# Senior_Design_2.net
KiCad netlist of a schematic drawn in EAGLE
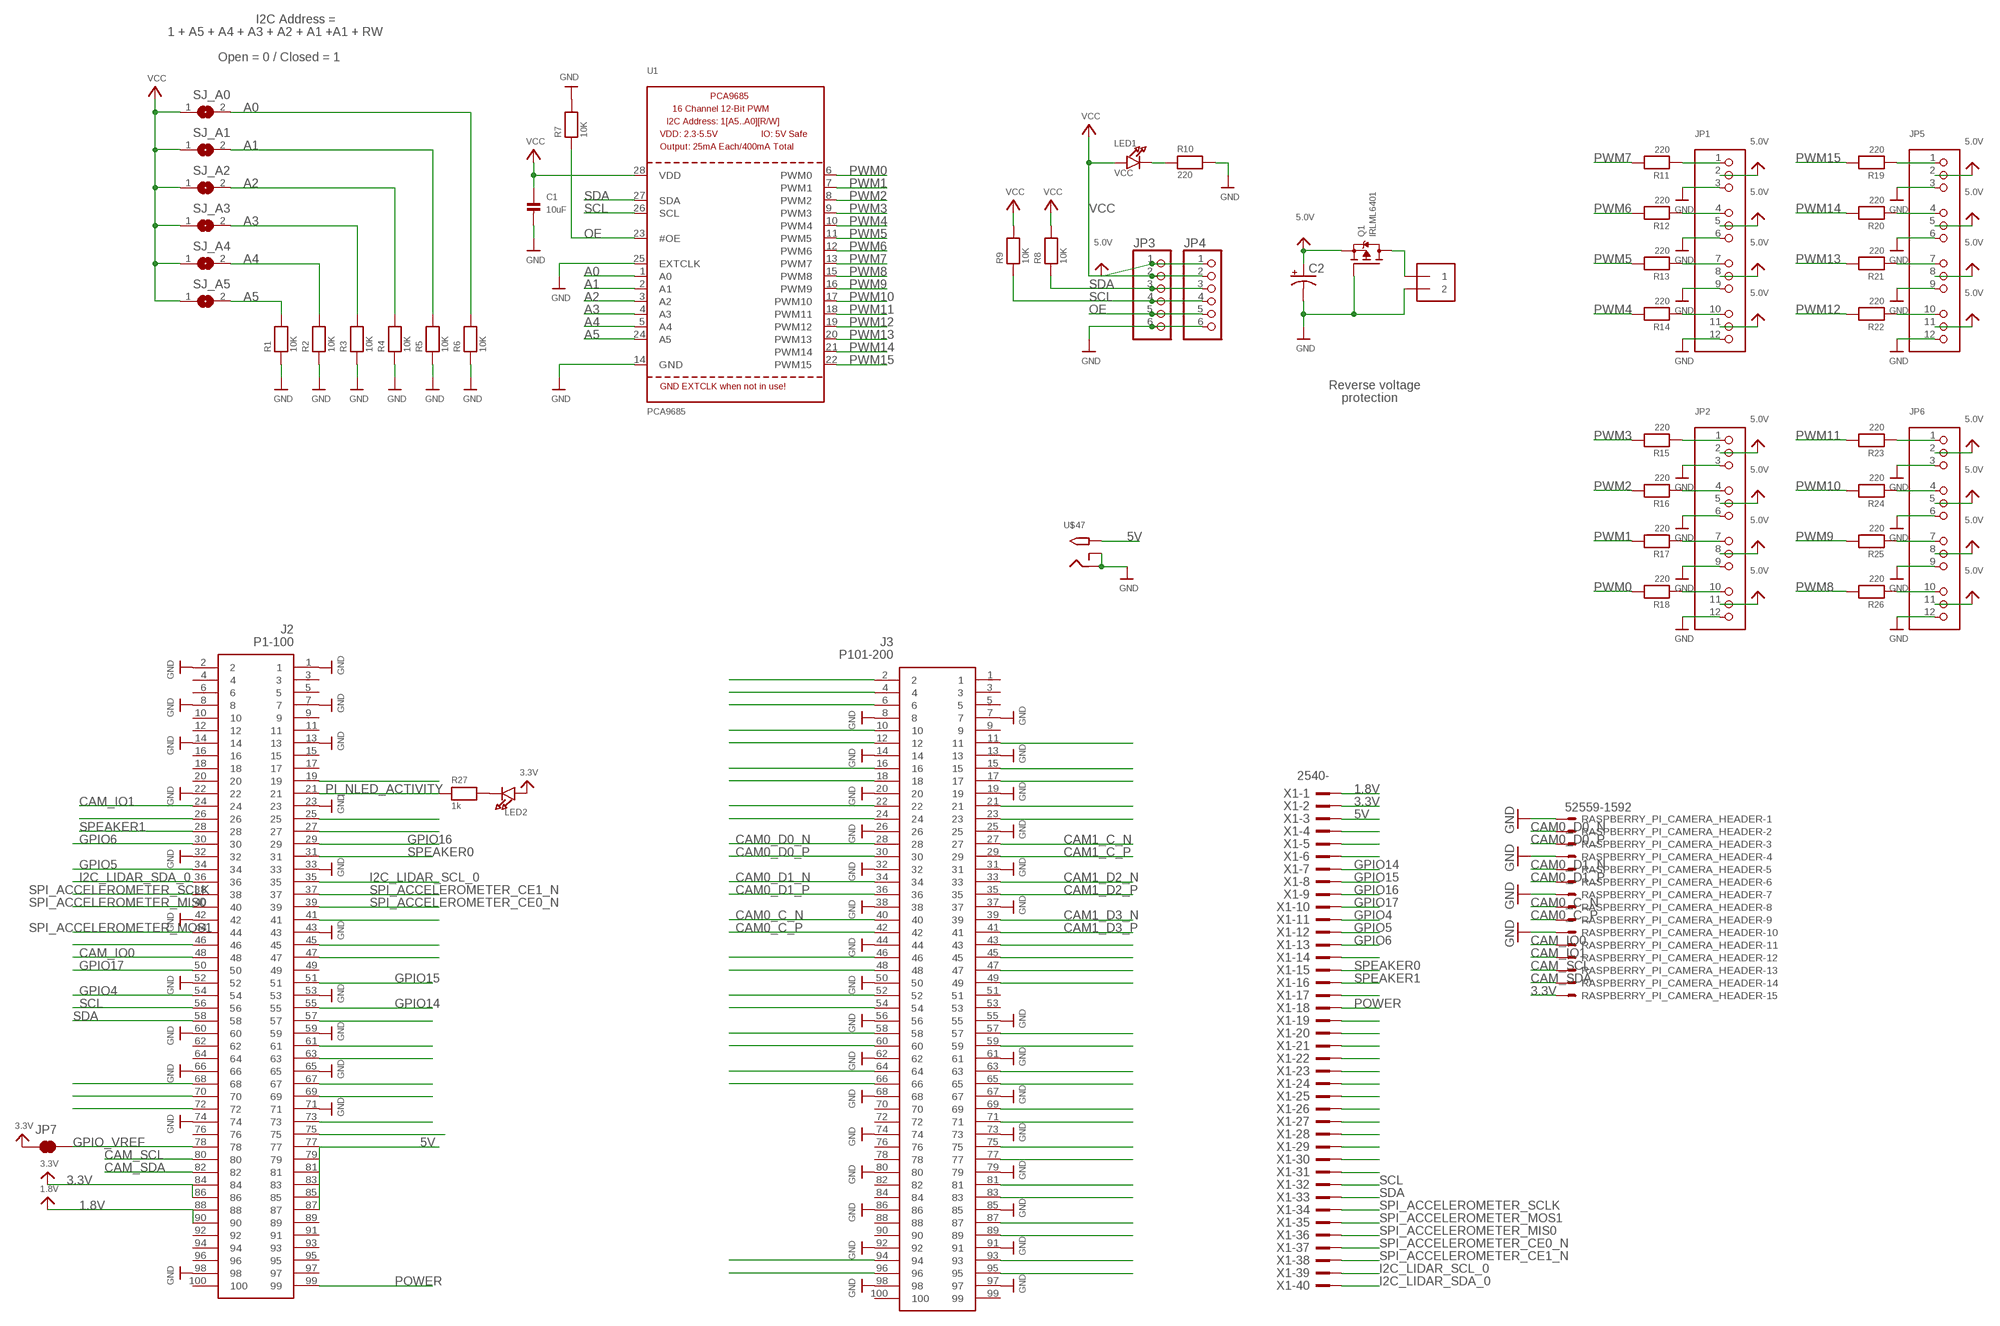
[diagram p0: schematic, sheet 1]

(export (version "E")
  (design (tool "Eeschema 10.0.6"))
  (components
    (comp (ref "C1")
      (value "10uF")
      (footprint "eagle-import:0805@1")
      (libsource (lib "eagle-import") (part "CAP_CERAMIC0805"))
    )
    (comp (ref "C2")
      (value "CPOL-USE3.5-8")
      (footprint "eagle-import:E3,5-8")
      (libsource (lib "eagle-import") (part "CPOL-USE3.5-8"))
    )
    (comp (ref "J1")
      (value "TERMBLOCK_1X2-3.5MM")
      (footprint "eagle-import:1X2-3.5MM")
      (libsource (lib "eagle-import") (part "TERMBLOCK_1X2-3.5MM"))
    )
    (comp (ref "J2")
      (value "P1-100")
      (footprint "eagle-import:DF40C100DS04V51")
      (fields
        (field (name "MANUFACTURER_PART_NUMBER") "DF40C-100DS-0.4V(51)")
        (field (name "MOUSER_PART_NUMBER") "798-DF40C100DS0.4V51")
        (field (name "MF") "VISHAY")
      )
      (libsource (lib "eagle-import") (part "DF40C-100DS-0.4V_51_"))
    )
    (comp (ref "J3")
      (value "P101-200")
      (footprint "eagle-import:DF40C100DS04V51")
      (fields
        (field (name "MANUFACTURER_PART_NUMBER") "DF40C-100DS-0.4V(51)")
        (field (name "MOUSER_PART_NUMBER") "798-DF40C100DS0.4V51")
      )
      (libsource (lib "eagle-import") (part "DF40C-100DS-0.4V_51_"))
    )
    (comp (ref "JP1")
      (value "HEADER-3X04")
      (footprint "eagle-import:3X04")
      (libsource (lib "eagle-import") (part "HEADER-3X04"))
    )
    (comp (ref "JP2")
      (value "HEADER-3X04")
      (footprint "eagle-import:3X04")
      (libsource (lib "eagle-import") (part "HEADER-3X04"))
    )
    (comp (ref "JP3")
      (value "PINHD-1X6CB")
      (footprint "eagle-import:1X06-CLEANBIG")
      (libsource (lib "eagle-import") (part "PINHD-1X6CB"))
    )
    (comp (ref "JP4")
      (value "PINHD-1X6CB")
      (footprint "eagle-import:1X06-CLEANBIG")
      (libsource (lib "eagle-import") (part "PINHD-1X6CB"))
    )
    (comp (ref "JP5")
      (value "HEADER-3X04")
      (footprint "eagle-import:3X04")
      (libsource (lib "eagle-import") (part "HEADER-3X04"))
    )
    (comp (ref "JP6")
      (value "HEADER-3X04")
      (footprint "eagle-import:3X04")
      (libsource (lib "eagle-import") (part "HEADER-3X04"))
    )
    (comp (ref "JP7")
      (value "JUMPER-SMT_2_NC_TRACE_NO-SILK")
      (footprint "eagle-import:SMT-JUMPER_2_NC_TRACE_NO-SILK")
      (libsource (lib "eagle-import") (part "JUMPER-SMT_2_NC_TRACE_NO-SILK"))
    )
    (comp (ref "LED1")
      (value "VCC")
      (footprint "eagle-import:CHIPLED_0805")
      (libsource (lib "eagle-import") (part "LED0805"))
    )
    (comp (ref "LED2")
      (value "LED0603")
      (footprint "eagle-import:CHIPLED_0603")
      (fields (field (name "MF") "OSRAM") (field (name "MPN") "LS Q976-NR-1"))
      (libsource (lib "eagle-import") (part "LED0603"))
    )
    (comp (ref "Q1")
      (value "IRLML6401")
      (footprint "eagle-import:SOT23-WIDE")
      (libsource (lib "eagle-import") (part "MOSFET-PWIDE"))
    )
    (comp (ref "R1")
      (value "10K")
      (footprint "eagle-import:0805")
      (libsource (lib "eagle-import") (part "RESISTOR0805"))
    )
    (comp (ref "R2")
      (value "10K")
      (footprint "eagle-import:0805")
      (libsource (lib "eagle-import") (part "RESISTOR0805"))
    )
    (comp (ref "R3")
      (value "10K")
      (footprint "eagle-import:0805")
      (libsource (lib "eagle-import") (part "RESISTOR0805"))
    )
    (comp (ref "R4")
      (value "10K")
      (footprint "eagle-import:0805")
      (libsource (lib "eagle-import") (part "RESISTOR0805"))
    )
    (comp (ref "R5")
      (value "10K")
      (footprint "eagle-import:0805")
      (libsource (lib "eagle-import") (part "RESISTOR0805"))
    )
    (comp (ref "R6")
      (value "10K")
      (footprint "eagle-import:0805")
      (libsource (lib "eagle-import") (part "RESISTOR0805"))
    )
    (comp (ref "R7")
      (value "10K")
      (footprint "eagle-import:0805")
      (libsource (lib "eagle-import") (part "RESISTOR0805"))
    )
    (comp (ref "R8")
      (value "10K")
      (footprint "eagle-import:0805")
      (libsource (lib "eagle-import") (part "RESISTOR0805"))
    )
    (comp (ref "R9")
      (value "10K")
      (footprint "eagle-import:0805")
      (libsource (lib "eagle-import") (part "RESISTOR0805"))
    )
    (comp (ref "R10")
      (value "220")
      (footprint "eagle-import:0805")
      (libsource (lib "eagle-import") (part "RESISTOR0805"))
    )
    (comp (ref "R11")
      (value "220")
      (footprint "eagle-import:0805")
      (libsource (lib "eagle-import") (part "RESISTOR0805"))
    )
    (comp (ref "R12")
      (value "220")
      (footprint "eagle-import:0805")
      (libsource (lib "eagle-import") (part "RESISTOR0805"))
    )
    (comp (ref "R13")
      (value "220")
      (footprint "eagle-import:0805")
      (libsource (lib "eagle-import") (part "RESISTOR0805"))
    )
    (comp (ref "R14")
      (value "220")
      (footprint "eagle-import:0805")
      (libsource (lib "eagle-import") (part "RESISTOR0805"))
    )
    (comp (ref "R15")
      (value "220")
      (footprint "eagle-import:0805")
      (libsource (lib "eagle-import") (part "RESISTOR0805"))
    )
    (comp (ref "R16")
      (value "220")
      (footprint "eagle-import:0805")
      (libsource (lib "eagle-import") (part "RESISTOR0805"))
    )
    (comp (ref "R17")
      (value "220")
      (footprint "eagle-import:0805")
      (libsource (lib "eagle-import") (part "RESISTOR0805"))
    )
    (comp (ref "R18")
      (value "220")
      (footprint "eagle-import:0805")
      (libsource (lib "eagle-import") (part "RESISTOR0805"))
    )
    (comp (ref "R19")
      (value "220")
      (footprint "eagle-import:0805")
      (libsource (lib "eagle-import") (part "RESISTOR0805"))
    )
    (comp (ref "R20")
      (value "220")
      (footprint "eagle-import:0805")
      (libsource (lib "eagle-import") (part "RESISTOR0805"))
    )
    (comp (ref "R21")
      (value "220")
      (footprint "eagle-import:0805")
      (libsource (lib "eagle-import") (part "RESISTOR0805"))
    )
    (comp (ref "R22")
      (value "220")
      (footprint "eagle-import:0805")
      (libsource (lib "eagle-import") (part "RESISTOR0805"))
    )
    (comp (ref "R23")
      (value "220")
      (footprint "eagle-import:0805")
      (libsource (lib "eagle-import") (part "RESISTOR0805"))
    )
    (comp (ref "R24")
      (value "220")
      (footprint "eagle-import:0805")
      (libsource (lib "eagle-import") (part "RESISTOR0805"))
    )
    (comp (ref "R25")
      (value "220")
      (footprint "eagle-import:0805")
      (libsource (lib "eagle-import") (part "RESISTOR0805"))
    )
    (comp (ref "R26")
      (value "220")
      (footprint "eagle-import:0805")
      (libsource (lib "eagle-import") (part "RESISTOR0805"))
    )
    (comp (ref "R27")
      (value "1k")
      (footprint "eagle-import:_0402MP")
      (fields (field (name "MF") "PANASONIC") (field (name "MPN") "ERJ-8ENF1001V"))
      (libsource (lib "eagle-import") (part "RESISTOR_0402MP"))
    )
    (comp (ref "RASPBERRY_PI_CAMERA_HEADER")
      (value "52559-1592")
      (footprint "eagle-import:52559-1592")
      (fields (field (name "MF") "MOLEX"))
      (libsource (lib "eagle-import") (part "52559-1592"))
    )
    (comp (ref "SJ_A0")
      (value "SOLDERJUMPERREFLOW_NOPASTE")
      (footprint "eagle-import:SOLDERJUMPER_REFLOW_NOPASTE")
      (libsource (lib "eagle-import") (part "SOLDERJUMPERREFLOW_NOPASTE"))
    )
    (comp (ref "SJ_A1")
      (value "SOLDERJUMPERREFLOW_NOPASTE")
      (footprint "eagle-import:SOLDERJUMPER_REFLOW_NOPASTE")
      (libsource (lib "eagle-import") (part "SOLDERJUMPERREFLOW_NOPASTE"))
    )
    (comp (ref "SJ_A2")
      (value "SOLDERJUMPERREFLOW_NOPASTE")
      (footprint "eagle-import:SOLDERJUMPER_REFLOW_NOPASTE")
      (libsource (lib "eagle-import") (part "SOLDERJUMPERREFLOW_NOPASTE"))
    )
    (comp (ref "SJ_A3")
      (value "SOLDERJUMPERREFLOW_NOPASTE")
      (footprint "eagle-import:SOLDERJUMPER_REFLOW_NOPASTE")
      (libsource (lib "eagle-import") (part "SOLDERJUMPERREFLOW_NOPASTE"))
    )
    (comp (ref "SJ_A4")
      (value "SOLDERJUMPERREFLOW_NOPASTE")
      (footprint "eagle-import:SOLDERJUMPER_REFLOW_NOPASTE")
      (libsource (lib "eagle-import") (part "SOLDERJUMPERREFLOW_NOPASTE"))
    )
    (comp (ref "SJ_A5")
      (value "SOLDERJUMPERREFLOW_NOPASTE")
      (footprint "eagle-import:SOLDERJUMPER_REFLOW_NOPASTE")
      (libsource (lib "eagle-import") (part "SOLDERJUMPERREFLOW_NOPASTE"))
    )
    (comp (ref "U$47")
      (value "2.1MMJACKTHM")
      (footprint "eagle-import:PJ-102A")
      (libsource (lib "eagle-import") (part "2.1MMJACKTHM"))
    )
    (comp (ref "U1")
      (value "PCA9685")
      (footprint "eagle-import:TSSOP28")
      (libsource (lib "eagle-import") (part "PCA9685"))
    )
    (comp (ref "X1")
      (value "2540-")
      (footprint "eagle-import:PAK100_2500-40")
      (libsource (lib "eagle-import") (part "2540-"))
    )
  )
  (nets
    (net (code "1") (name "/5V") (class "Default")
      (node (ref "J2") (pin "77") (pinfunction "77_77") (pintype "bidirectional"))
      (node (ref "J2") (pin "79") (pinfunction "79_79") (pintype "bidirectional"))
      (node (ref "J2") (pin "81") (pinfunction "81_81") (pintype "bidirectional"))
      (node (ref "J2") (pin "83") (pinfunction "83_83") (pintype "bidirectional"))
      (node (ref "J2") (pin "85") (pinfunction "85_85") (pintype "bidirectional"))
      (node (ref "J2") (pin "87") (pinfunction "87_87") (pintype "bidirectional"))
      (node (ref "U$47") (pin "TIP") (pinfunction "TIP_TIP") (pintype "bidirectional"))
      (node (ref "X1") (pin "3") (pinfunction "KL_3") (pintype "passive"))
    )
    (net (code "2") (name "/A0") (class "Default")
      (node (ref "R6") (pin "2") (pinfunction "2_2") (pintype "passive"))
      (node (ref "SJ_A0") (pin "2") (pinfunction "2_2") (pintype "passive"))
      (node (ref "U1") (pin "1") (pinfunction "A0_1") (pintype "bidirectional"))
    )
    (net (code "3") (name "/A1") (class "Default")
      (node (ref "R5") (pin "2") (pinfunction "2_2") (pintype "passive"))
      (node (ref "SJ_A1") (pin "2") (pinfunction "2_2") (pintype "passive"))
      (node (ref "U1") (pin "2") (pinfunction "A1_2") (pintype "bidirectional"))
    )
    (net (code "4") (name "/A2") (class "Default")
      (node (ref "R4") (pin "2") (pinfunction "2_2") (pintype "passive"))
      (node (ref "SJ_A2") (pin "2") (pinfunction "2_2") (pintype "passive"))
      (node (ref "U1") (pin "3") (pinfunction "A2_3") (pintype "bidirectional"))
    )
    (net (code "5") (name "/A3") (class "Default")
      (node (ref "R3") (pin "2") (pinfunction "2_2") (pintype "passive"))
      (node (ref "SJ_A3") (pin "2") (pinfunction "2_2") (pintype "passive"))
      (node (ref "U1") (pin "4") (pinfunction "A3_4") (pintype "bidirectional"))
    )
    (net (code "6") (name "/A4") (class "Default")
      (node (ref "R2") (pin "2") (pinfunction "2_2") (pintype "passive"))
      (node (ref "SJ_A4") (pin "2") (pinfunction "2_2") (pintype "passive"))
      (node (ref "U1") (pin "5") (pinfunction "A4_5") (pintype "bidirectional"))
    )
    (net (code "7") (name "/A5") (class "Default")
      (node (ref "R1") (pin "2") (pinfunction "2_2") (pintype "passive"))
      (node (ref "SJ_A5") (pin "2") (pinfunction "2_2") (pintype "passive"))
      (node (ref "U1") (pin "24") (pinfunction "A5_24") (pintype "bidirectional"))
    )
    (net (code "8") (name "/CAM0_C_N") (class "Default")
      (node (ref "J3") (pin "40") (pinfunction "40_40") (pintype "bidirectional"))
      (node (ref "RASPBERRY_PI_CAMERA_HEADER") (pin "8") (pinfunction "S_8") (pintype "passive"))
    )
    (net (code "9") (name "/CAM0_C_P") (class "Default")
      (node (ref "J3") (pin "42") (pinfunction "42_42") (pintype "bidirectional"))
      (node (ref "RASPBERRY_PI_CAMERA_HEADER") (pin "9") (pinfunction "S_9") (pintype "passive"))
    )
    (net (code "10") (name "/CAM0_D0_N") (class "Default")
      (node (ref "J3") (pin "28") (pinfunction "28_28") (pintype "bidirectional"))
      (node (ref "RASPBERRY_PI_CAMERA_HEADER") (pin "2") (pinfunction "S_2") (pintype "passive"))
    )
    (net (code "11") (name "/CAM0_D0_P") (class "Default")
      (node (ref "J3") (pin "30") (pinfunction "30_30") (pintype "bidirectional"))
      (node (ref "RASPBERRY_PI_CAMERA_HEADER") (pin "3") (pinfunction "S_3") (pintype "passive"))
    )
    (net (code "12") (name "/CAM0_D1_N") (class "Default")
      (node (ref "J3") (pin "34") (pinfunction "34_34") (pintype "bidirectional"))
      (node (ref "RASPBERRY_PI_CAMERA_HEADER") (pin "5") (pinfunction "S_5") (pintype "passive"))
    )
    (net (code "13") (name "/CAM0_D1_P") (class "Default")
      (node (ref "J3") (pin "36") (pinfunction "36_36") (pintype "bidirectional"))
      (node (ref "RASPBERRY_PI_CAMERA_HEADER") (pin "6") (pinfunction "S_6") (pintype "passive"))
    )
    (net (code "14") (name "/CAM1_C_N") (class "Default")
      (node (ref "J3") (pin "27") (pinfunction "27_27") (pintype "bidirectional"))
    )
    (net (code "15") (name "/CAM1_C_P") (class "Default")
      (node (ref "J3") (pin "29") (pinfunction "29_29") (pintype "bidirectional"))
    )
    (net (code "16") (name "/CAM1_D2_N") (class "Default")
      (node (ref "J3") (pin "33") (pinfunction "33_33") (pintype "bidirectional"))
    )
    (net (code "17") (name "/CAM1_D2_P") (class "Default")
      (node (ref "J3") (pin "35") (pinfunction "35_35") (pintype "bidirectional"))
    )
    (net (code "18") (name "/CAM1_D3_N") (class "Default")
      (node (ref "J3") (pin "39") (pinfunction "39_39") (pintype "bidirectional"))
    )
    (net (code "19") (name "/CAM1_D3_P") (class "Default")
      (node (ref "J3") (pin "41") (pinfunction "41_41") (pintype "bidirectional"))
    )
    (net (code "20") (name "/CAM_IO0") (class "Default")
      (node (ref "J2") (pin "48") (pinfunction "48_48") (pintype "bidirectional"))
      (node (ref "RASPBERRY_PI_CAMERA_HEADER") (pin "11") (pinfunction "S_11") (pintype "passive"))
    )
    (net (code "21") (name "/CAM_IO1") (class "Default")
      (node (ref "J2") (pin "24") (pinfunction "24_24") (pintype "bidirectional"))
      (node (ref "RASPBERRY_PI_CAMERA_HEADER") (pin "12") (pinfunction "S_12") (pintype "passive"))
    )
    (net (code "22") (name "/CAM_SCL") (class "Default")
      (node (ref "J2") (pin "80") (pinfunction "80_80") (pintype "bidirectional"))
      (node (ref "RASPBERRY_PI_CAMERA_HEADER") (pin "13") (pinfunction "S_13") (pintype "passive"))
    )
    (net (code "23") (name "/CAM_SDA") (class "Default")
      (node (ref "J2") (pin "82") (pinfunction "82_82") (pintype "bidirectional"))
      (node (ref "RASPBERRY_PI_CAMERA_HEADER") (pin "14") (pinfunction "S_14") (pintype "passive"))
    )
    (net (code "24") (name "/GPIO4") (class "Default")
      (node (ref "J2") (pin "54") (pinfunction "54_54") (pintype "bidirectional"))
      (node (ref "X1") (pin "11") (pinfunction "KL_11") (pintype "passive"))
    )
    (net (code "25") (name "/GPIO5") (class "Default")
      (node (ref "J2") (pin "34") (pinfunction "34_34") (pintype "bidirectional"))
      (node (ref "X1") (pin "12") (pinfunction "KL_12") (pintype "passive"))
    )
    (net (code "26") (name "/GPIO6") (class "Default")
      (node (ref "J2") (pin "30") (pinfunction "30_30") (pintype "bidirectional"))
      (node (ref "X1") (pin "13") (pinfunction "KL_13") (pintype "passive"))
    )
    (net (code "27") (name "/GPIO14") (class "Default")
      (node (ref "J2") (pin "55") (pinfunction "55_55") (pintype "bidirectional"))
      (node (ref "X1") (pin "7") (pinfunction "KL_7") (pintype "passive"))
    )
    (net (code "28") (name "/GPIO15") (class "Default")
      (node (ref "J2") (pin "51") (pinfunction "51_51") (pintype "bidirectional"))
      (node (ref "X1") (pin "8") (pinfunction "KL_8") (pintype "passive"))
    )
    (net (code "29") (name "/GPIO16") (class "Default")
      (node (ref "J2") (pin "29") (pinfunction "29_29") (pintype "bidirectional"))
      (node (ref "X1") (pin "9") (pinfunction "KL_9") (pintype "passive"))
    )
    (net (code "30") (name "/GPIO17") (class "Default")
      (node (ref "J2") (pin "50") (pinfunction "50_50") (pintype "bidirectional"))
      (node (ref "X1") (pin "10") (pinfunction "KL_10") (pintype "passive"))
    )
    (net (code "31") (name "/GPIO_VREF") (class "Default")
      (node (ref "J2") (pin "78") (pinfunction "78_78") (pintype "bidirectional"))
      (node (ref "JP7") (pin "2") (pinfunction "2_2") (pintype "passive"))
    )
    (net (code "32") (name "/I2C_LIDAR_SCL_0") (class "Default")
      (node (ref "J2") (pin "35") (pinfunction "35_35") (pintype "bidirectional"))
      (node (ref "X1") (pin "39") (pinfunction "KL_39") (pintype "passive"))
    )
    (net (code "33") (name "/I2C_LIDAR_SDA_0") (class "Default")
      (node (ref "J2") (pin "36") (pinfunction "36_36") (pintype "bidirectional"))
      (node (ref "X1") (pin "40") (pinfunction "KL_40") (pintype "passive"))
    )
    (net (code "34") (name "/OE") (class "Default")
      (node (ref "JP3") (pin "5") (pinfunction "5_5") (pintype "passive"))
      (node (ref "JP4") (pin "5") (pinfunction "5_5") (pintype "passive"))
      (node (ref "R7") (pin "1") (pinfunction "1_1") (pintype "passive"))
      (node (ref "U1") (pin "23") (pinfunction "#OE_23") (pintype "input"))
    )
    (net (code "35") (name "/PI_NLED_ACTIVITY") (class "Default")
      (node (ref "J2") (pin "21") (pinfunction "21_21") (pintype "bidirectional"))
      (node (ref "R27") (pin "1") (pinfunction "1_1") (pintype "passive"))
    )
    (net (code "36") (name "/POWER") (class "Default")
      (node (ref "J2") (pin "99") (pinfunction "99_99") (pintype "bidirectional"))
      (node (ref "X1") (pin "18") (pinfunction "KL_18") (pintype "passive"))
    )
    (net (code "37") (name "/PWM0") (class "Default")
      (node (ref "R18") (pin "2") (pinfunction "2_2") (pintype "passive"))
      (node (ref "U1") (pin "6") (pinfunction "PWM0_6") (pintype "output"))
    )
    (net (code "38") (name "/PWM1") (class "Default")
      (node (ref "R17") (pin "2") (pinfunction "2_2") (pintype "passive"))
      (node (ref "U1") (pin "7") (pinfunction "PWM1_7") (pintype "output"))
    )
    (net (code "39") (name "/PWM2") (class "Default")
      (node (ref "R16") (pin "2") (pinfunction "2_2") (pintype "passive"))
      (node (ref "U1") (pin "8") (pinfunction "PWM2_8") (pintype "output"))
    )
    (net (code "40") (name "/PWM3") (class "Default")
      (node (ref "R15") (pin "2") (pinfunction "2_2") (pintype "passive"))
      (node (ref "U1") (pin "9") (pinfunction "PWM3_9") (pintype "output"))
    )
    (net (code "41") (name "/PWM4") (class "Default")
      (node (ref "R14") (pin "2") (pinfunction "2_2") (pintype "passive"))
      (node (ref "U1") (pin "10") (pinfunction "PWM4_10") (pintype "output"))
    )
    (net (code "42") (name "/PWM5") (class "Default")
      (node (ref "R13") (pin "2") (pinfunction "2_2") (pintype "passive"))
      (node (ref "U1") (pin "11") (pinfunction "PWM5_11") (pintype "output"))
    )
    (net (code "43") (name "/PWM6") (class "Default")
      (node (ref "R12") (pin "2") (pinfunction "2_2") (pintype "passive"))
      (node (ref "U1") (pin "12") (pinfunction "PWM6_12") (pintype "output"))
    )
    (net (code "44") (name "/PWM7") (class "Default")
      (node (ref "R11") (pin "2") (pinfunction "2_2") (pintype "passive"))
      (node (ref "U1") (pin "13") (pinfunction "PWM7_13") (pintype "output"))
    )
    (net (code "45") (name "/PWM8") (class "Default")
      (node (ref "R26") (pin "2") (pinfunction "2_2") (pintype "passive"))
      (node (ref "U1") (pin "15") (pinfunction "PWM8_15") (pintype "output"))
    )
    (net (code "46") (name "/PWM9") (class "Default")
      (node (ref "R25") (pin "2") (pinfunction "2_2") (pintype "passive"))
      (node (ref "U1") (pin "16") (pinfunction "PWM9_16") (pintype "output"))
    )
    (net (code "47") (name "/PWM10") (class "Default")
      (node (ref "R24") (pin "2") (pinfunction "2_2") (pintype "passive"))
      (node (ref "U1") (pin "17") (pinfunction "PWM10_17") (pintype "output"))
    )
    (net (code "48") (name "/PWM11") (class "Default")
      (node (ref "R23") (pin "2") (pinfunction "2_2") (pintype "passive"))
      (node (ref "U1") (pin "18") (pinfunction "PWM11_18") (pintype "output"))
    )
    (net (code "49") (name "/PWM12") (class "Default")
      (node (ref "R22") (pin "2") (pinfunction "2_2") (pintype "passive"))
      (node (ref "U1") (pin "19") (pinfunction "PWM12_19") (pintype "output"))
    )
    (net (code "50") (name "/PWM13") (class "Default")
      (node (ref "R21") (pin "2") (pinfunction "2_2") (pintype "passive"))
      (node (ref "U1") (pin "20") (pinfunction "PWM13_20") (pintype "output"))
    )
    (net (code "51") (name "/PWM14") (class "Default")
      (node (ref "R20") (pin "2") (pinfunction "2_2") (pintype "passive"))
      (node (ref "U1") (pin "21") (pinfunction "PWM14_21") (pintype "output"))
    )
    (net (code "52") (name "/PWM15") (class "Default")
      (node (ref "R19") (pin "2") (pinfunction "2_2") (pintype "passive"))
      (node (ref "U1") (pin "22") (pinfunction "PWM15_22") (pintype "output"))
    )
    (net (code "53") (name "/SCL") (class "Default")
      (node (ref "J2") (pin "56") (pinfunction "56_56") (pintype "bidirectional"))
      (node (ref "JP3") (pin "4") (pinfunction "4_4") (pintype "passive"))
      (node (ref "JP4") (pin "4") (pinfunction "4_4") (pintype "passive"))
      (node (ref "R9") (pin "1") (pinfunction "1_1") (pintype "passive"))
      (node (ref "U1") (pin "26") (pinfunction "SCL_26") (pintype "bidirectional"))
      (node (ref "X1") (pin "32") (pinfunction "KL_32") (pintype "passive"))
    )
    (net (code "54") (name "/SDA") (class "Default")
      (node (ref "J2") (pin "58") (pinfunction "58_58") (pintype "bidirectional"))
      (node (ref "JP3") (pin "3") (pinfunction "3_3") (pintype "passive"))
      (node (ref "JP4") (pin "3") (pinfunction "3_3") (pintype "passive"))
      (node (ref "R8") (pin "1") (pinfunction "1_1") (pintype "passive"))
      (node (ref "U1") (pin "27") (pinfunction "SDA_27") (pintype "bidirectional"))
      (node (ref "X1") (pin "33") (pinfunction "KL_33") (pintype "passive"))
    )
    (net (code "55") (name "/SPEAKER0") (class "Default")
      (node (ref "J2") (pin "31") (pinfunction "31_31") (pintype "bidirectional"))
      (node (ref "X1") (pin "15") (pinfunction "KL_15") (pintype "passive"))
    )
    (net (code "56") (name "/SPEAKER1") (class "Default")
      (node (ref "J2") (pin "28") (pinfunction "28_28") (pintype "bidirectional"))
      (node (ref "X1") (pin "16") (pinfunction "KL_16") (pintype "passive"))
    )
    (net (code "57") (name "/SPI_ACCELEROMETER_CE0_N") (class "Default")
      (node (ref "J2") (pin "39") (pinfunction "39_39") (pintype "bidirectional"))
      (node (ref "X1") (pin "37") (pinfunction "KL_37") (pintype "passive"))
    )
    (net (code "58") (name "/SPI_ACCELEROMETER_CE1_N") (class "Default")
      (node (ref "J2") (pin "37") (pinfunction "37_37") (pintype "bidirectional"))
      (node (ref "X1") (pin "38") (pinfunction "KL_38") (pintype "passive"))
    )
    (net (code "59") (name "/SPI_ACCELEROMETER_MIS0") (class "Default")
      (node (ref "J2") (pin "40") (pinfunction "40_40") (pintype "bidirectional"))
      (node (ref "X1") (pin "36") (pinfunction "KL_36") (pintype "passive"))
    )
    (net (code "60") (name "/SPI_ACCELEROMETER_MOS1") (class "Default")
      (node (ref "J2") (pin "44") (pinfunction "44_44") (pintype "bidirectional"))
      (node (ref "X1") (pin "35") (pinfunction "KL_35") (pintype "passive"))
    )
    (net (code "61") (name "/SPI_ACCELEROMETER_SCLK") (class "Default")
      (node (ref "J2") (pin "38") (pinfunction "38_38") (pintype "bidirectional"))
      (node (ref "X1") (pin "34") (pinfunction "KL_34") (pintype "passive"))
    )
    (net (code "62") (name "1.8V") (class "Default")
      (node (ref "J2") (pin "88") (pinfunction "88_88") (pintype "bidirectional"))
      (node (ref "J2") (pin "90") (pinfunction "90_90") (pintype "bidirectional"))
      (node (ref "X1") (pin "1") (pinfunction "KL_1") (pintype "passive"))
    )
    (net (code "63") (name "3.3V") (class "Default")
      (node (ref "J2") (pin "84") (pinfunction "84_84") (pintype "bidirectional"))
      (node (ref "J2") (pin "86") (pinfunction "86_86") (pintype "bidirectional"))
      (node (ref "JP7") (pin "1") (pinfunction "1_1") (pintype "passive"))
      (node (ref "LED2") (pin "A") (pinfunction "A_A") (pintype "passive"))
      (node (ref "RASPBERRY_PI_CAMERA_HEADER") (pin "15") (pinfunction "S_15") (pintype "passive"))
      (node (ref "X1") (pin "2") (pinfunction "KL_2") (pintype "passive"))
    )
    (net (code "64") (name "5.0V") (class "Default")
      (node (ref "C2") (pin "+") (pinfunction "+_+") (pintype "passive"))
      (node (ref "JP1") (pin "11") (pinfunction "11_11") (pintype "passive"))
      (node (ref "JP1") (pin "2") (pinfunction "2_2") (pintype "passive"))
      (node (ref "JP1") (pin "5") (pinfunction "5_5") (pintype "passive"))
      (node (ref "JP1") (pin "8") (pinfunction "8_8") (pintype "passive"))
      (node (ref "JP2") (pin "11") (pinfunction "11_11") (pintype "passive"))
      (node (ref "JP2") (pin "2") (pinfunction "2_2") (pintype "passive"))
      (node (ref "JP2") (pin "5") (pinfunction "5_5") (pintype "passive"))
      (node (ref "JP2") (pin "8") (pinfunction "8_8") (pintype "passive"))
      (node (ref "JP3") (pin "1") (pinfunction "1_1") (pintype "passive"))
      (node (ref "JP4") (pin "1") (pinfunction "1_1") (pintype "passive"))
      (node (ref "JP5") (pin "11") (pinfunction "11_11") (pintype "passive"))
      (node (ref "JP5") (pin "2") (pinfunction "2_2") (pintype "passive"))
      (node (ref "JP5") (pin "5") (pinfunction "5_5") (pintype "passive"))
      (node (ref "JP5") (pin "8") (pinfunction "8_8") (pintype "passive"))
      (node (ref "JP6") (pin "11") (pinfunction "11_11") (pintype "passive"))
      (node (ref "JP6") (pin "2") (pinfunction "2_2") (pintype "passive"))
      (node (ref "JP6") (pin "5") (pinfunction "5_5") (pintype "passive"))
      (node (ref "JP6") (pin "8") (pinfunction "8_8") (pintype "passive"))
      (node (ref "Q1") (pin "2") (pinfunction "S_2") (pintype "passive"))
    )
    (net (code "65") (name "GND") (class "Default")
      (node (ref "C1") (pin "2") (pinfunction "P$2_2") (pintype "passive"))
      (node (ref "C2") (pin "-") (pinfunction "-_-") (pintype "passive"))
      (node (ref "J1") (pin "2") (pinfunction "2_2") (pintype "passive"))
      (node (ref "J2") (pin "1") (pinfunction "1_1") (pintype "bidirectional"))
      (node (ref "J2") (pin "13") (pinfunction "13_13") (pintype "bidirectional"))
      (node (ref "J2") (pin "14") (pinfunction "14_14") (pintype "bidirectional"))
      (node (ref "J2") (pin "2") (pinfunction "2_2") (pintype "bidirectional"))
      (node (ref "J2") (pin "22") (pinfunction "22_22") (pintype "bidirectional"))
      (node (ref "J2") (pin "23") (pinfunction "23_23") (pintype "bidirectional"))
      (node (ref "J2") (pin "32") (pinfunction "32_32") (pintype "bidirectional"))
      (node (ref "J2") (pin "33") (pinfunction "33_33") (pintype "bidirectional"))
      (node (ref "J2") (pin "42") (pinfunction "42_42") (pintype "bidirectional"))
      (node (ref "J2") (pin "43") (pinfunction "43_43") (pintype "bidirectional"))
      (node (ref "J2") (pin "52") (pinfunction "52_52") (pintype "bidirectional"))
      (node (ref "J2") (pin "53") (pinfunction "53_53") (pintype "bidirectional"))
      (node (ref "J2") (pin "59") (pinfunction "59_59") (pintype "bidirectional"))
      (node (ref "J2") (pin "60") (pinfunction "60_60") (pintype "bidirectional"))
      (node (ref "J2") (pin "65") (pinfunction "65_65") (pintype "bidirectional"))
      (node (ref "J2") (pin "66") (pinfunction "66_66") (pintype "bidirectional"))
      (node (ref "J2") (pin "7") (pinfunction "7_7") (pintype "bidirectional"))
      (node (ref "J2") (pin "71") (pinfunction "71_71") (pintype "bidirectional"))
      (node (ref "J2") (pin "74") (pinfunction "74_74") (pintype "bidirectional"))
      (node (ref "J2") (pin "8") (pinfunction "8_8") (pintype "bidirectional"))
      (node (ref "J2") (pin "98") (pinfunction "98_98") (pintype "bidirectional"))
      (node (ref "J3") (pin "13") (pinfunction "13_13") (pintype "bidirectional"))
      (node (ref "J3") (pin "14") (pinfunction "14_14") (pintype "bidirectional"))
      (node (ref "J3") (pin "19") (pinfunction "19_19") (pintype "bidirectional"))
      (node (ref "J3") (pin "20") (pinfunction "20_20") (pintype "bidirectional"))
      (node (ref "J3") (pin "25") (pinfunction "25_25") (pintype "bidirectional"))
      (node (ref "J3") (pin "26") (pinfunction "26_26") (pintype "bidirectional"))
      (node (ref "J3") (pin "31") (pinfunction "31_31") (pintype "bidirectional"))
      (node (ref "J3") (pin "32") (pinfunction "32_32") (pintype "bidirectional"))
      (node (ref "J3") (pin "37") (pinfunction "37_37") (pintype "bidirectional"))
      (node (ref "J3") (pin "38") (pinfunction "38_38") (pintype "bidirectional"))
      (node (ref "J3") (pin "44") (pinfunction "44_44") (pintype "bidirectional"))
      (node (ref "J3") (pin "50") (pinfunction "50_50") (pintype "bidirectional"))
      (node (ref "J3") (pin "55") (pinfunction "55_55") (pintype "bidirectional"))
      (node (ref "J3") (pin "56") (pinfunction "56_56") (pintype "bidirectional"))
      (node (ref "J3") (pin "61") (pinfunction "61_61") (pintype "bidirectional"))
      (node (ref "J3") (pin "62") (pinfunction "62_62") (pintype "bidirectional"))
      (node (ref "J3") (pin "67") (pinfunction "67_67") (pintype "bidirectional"))
      (node (ref "J3") (pin "68") (pinfunction "68_68") (pintype "bidirectional"))
      (node (ref "J3") (pin "7") (pinfunction "7_7") (pintype "bidirectional"))
      (node (ref "J3") (pin "73") (pinfunction "73_73") (pintype "bidirectional"))
      (node (ref "J3") (pin "74") (pinfunction "74_74") (pintype "bidirectional"))
      (node (ref "J3") (pin "79") (pinfunction "79_79") (pintype "bidirectional"))
      (node (ref "J3") (pin "8") (pinfunction "8_8") (pintype "bidirectional"))
      (node (ref "J3") (pin "80") (pinfunction "80_80") (pintype "bidirectional"))
      (node (ref "J3") (pin "85") (pinfunction "85_85") (pintype "bidirectional"))
      (node (ref "J3") (pin "86") (pinfunction "86_86") (pintype "bidirectional"))
      (node (ref "J3") (pin "91") (pinfunction "91_91") (pintype "bidirectional"))
      (node (ref "J3") (pin "92") (pinfunction "92_92") (pintype "bidirectional"))
      (node (ref "J3") (pin "97") (pinfunction "97_97") (pintype "bidirectional"))
      (node (ref "J3") (pin "98") (pinfunction "98_98") (pintype "bidirectional"))
      (node (ref "JP1") (pin "12") (pinfunction "12_12") (pintype "passive"))
      (node (ref "JP1") (pin "3") (pinfunction "3_3") (pintype "passive"))
      (node (ref "JP1") (pin "6") (pinfunction "6_6") (pintype "passive"))
      (node (ref "JP1") (pin "9") (pinfunction "9_9") (pintype "passive"))
      (node (ref "JP2") (pin "12") (pinfunction "12_12") (pintype "passive"))
      (node (ref "JP2") (pin "3") (pinfunction "3_3") (pintype "passive"))
      (node (ref "JP2") (pin "6") (pinfunction "6_6") (pintype "passive"))
      (node (ref "JP2") (pin "9") (pinfunction "9_9") (pintype "passive"))
      (node (ref "JP3") (pin "6") (pinfunction "6_6") (pintype "passive"))
      (node (ref "JP4") (pin "6") (pinfunction "6_6") (pintype "passive"))
      (node (ref "JP5") (pin "12") (pinfunction "12_12") (pintype "passive"))
      (node (ref "JP5") (pin "3") (pinfunction "3_3") (pintype "passive"))
      (node (ref "JP5") (pin "6") (pinfunction "6_6") (pintype "passive"))
      (node (ref "JP5") (pin "9") (pinfunction "9_9") (pintype "passive"))
      (node (ref "JP6") (pin "12") (pinfunction "12_12") (pintype "passive"))
      (node (ref "JP6") (pin "3") (pinfunction "3_3") (pintype "passive"))
      (node (ref "JP6") (pin "6") (pinfunction "6_6") (pintype "passive"))
      (node (ref "JP6") (pin "9") (pinfunction "9_9") (pintype "passive"))
      (node (ref "Q1") (pin "1") (pinfunction "G_1") (pintype "passive"))
      (node (ref "R1") (pin "1") (pinfunction "1_1") (pintype "passive"))
      (node (ref "R10") (pin "2") (pinfunction "2_2") (pintype "passive"))
      (node (ref "R2") (pin "1") (pinfunction "1_1") (pintype "passive"))
      (node (ref "R3") (pin "1") (pinfunction "1_1") (pintype "passive"))
      (node (ref "R4") (pin "1") (pinfunction "1_1") (pintype "passive"))
      (node (ref "R5") (pin "1") (pinfunction "1_1") (pintype "passive"))
      (node (ref "R6") (pin "1") (pinfunction "1_1") (pintype "passive"))
      (node (ref "R7") (pin "2") (pinfunction "2_2") (pintype "passive"))
      (node (ref "RASPBERRY_PI_CAMERA_HEADER") (pin "1") (pinfunction "S_1") (pintype "passive"))
      (node (ref "RASPBERRY_PI_CAMERA_HEADER") (pin "10") (pinfunction "S_10") (pintype "passive"))
      (node (ref "RASPBERRY_PI_CAMERA_HEADER") (pin "4") (pinfunction "S_4") (pintype "passive"))
      (node (ref "RASPBERRY_PI_CAMERA_HEADER") (pin "7") (pinfunction "S_7") (pintype "passive"))
      (node (ref "U$47") (pin "RING") (pinfunction "RING_RING") (pintype "bidirectional"))
      (node (ref "U$47") (pin "RING_SW") (pinfunction "RING_SW_RING_SW") (pintype "bidirectional"))
      (node (ref "U1") (pin "14") (pinfunction "GND_14") (pintype "power_in"))
      (node (ref "U1") (pin "25") (pinfunction "EXTCLK_25") (pintype "input"))
    )
    (net (code "66") (name "Net-(JP1-Pad1)") (class "Default")
      (node (ref "JP1") (pin "1") (pinfunction "1_1") (pintype "passive"))
      (node (ref "R11") (pin "1") (pinfunction "1_1") (pintype "passive"))
    )
    (net (code "67") (name "Net-(JP1-Pad4)") (class "Default")
      (node (ref "JP1") (pin "4") (pinfunction "4_4") (pintype "passive"))
      (node (ref "R12") (pin "1") (pinfunction "1_1") (pintype "passive"))
    )
    (net (code "68") (name "Net-(JP1-Pad7)") (class "Default")
      (node (ref "JP1") (pin "7") (pinfunction "7_7") (pintype "passive"))
      (node (ref "R13") (pin "1") (pinfunction "1_1") (pintype "passive"))
    )
    (net (code "69") (name "Net-(JP1-Pad10)") (class "Default")
      (node (ref "JP1") (pin "10") (pinfunction "10_10") (pintype "passive"))
      (node (ref "R14") (pin "1") (pinfunction "1_1") (pintype "passive"))
    )
    (net (code "70") (name "Net-(JP2-Pad1)") (class "Default")
      (node (ref "JP2") (pin "1") (pinfunction "1_1") (pintype "passive"))
      (node (ref "R15") (pin "1") (pinfunction "1_1") (pintype "passive"))
    )
    (net (code "71") (name "Net-(JP2-Pad4)") (class "Default")
      (node (ref "JP2") (pin "4") (pinfunction "4_4") (pintype "passive"))
      (node (ref "R16") (pin "1") (pinfunction "1_1") (pintype "passive"))
    )
    (net (code "72") (name "Net-(JP2-Pad7)") (class "Default")
      (node (ref "JP2") (pin "7") (pinfunction "7_7") (pintype "passive"))
      (node (ref "R17") (pin "1") (pinfunction "1_1") (pintype "passive"))
    )
    (net (code "73") (name "Net-(JP2-Pad10)") (class "Default")
      (node (ref "JP2") (pin "10") (pinfunction "10_10") (pintype "passive"))
      (node (ref "R18") (pin "1") (pinfunction "1_1") (pintype "passive"))
    )
    (net (code "74") (name "Net-(JP5-Pad1)") (class "Default")
      (node (ref "JP5") (pin "1") (pinfunction "1_1") (pintype "passive"))
      (node (ref "R19") (pin "1") (pinfunction "1_1") (pintype "passive"))
    )
    (net (code "75") (name "Net-(JP5-Pad4)") (class "Default")
      (node (ref "JP5") (pin "4") (pinfunction "4_4") (pintype "passive"))
      (node (ref "R20") (pin "1") (pinfunction "1_1") (pintype "passive"))
    )
    (net (code "76") (name "Net-(JP5-Pad7)") (class "Default")
      (node (ref "JP5") (pin "7") (pinfunction "7_7") (pintype "passive"))
      (node (ref "R21") (pin "1") (pinfunction "1_1") (pintype "passive"))
    )
    (net (code "77") (name "Net-(JP5-Pad10)") (class "Default")
      (node (ref "JP5") (pin "10") (pinfunction "10_10") (pintype "passive"))
      (node (ref "R22") (pin "1") (pinfunction "1_1") (pintype "passive"))
    )
    (net (code "78") (name "Net-(JP6-Pad1)") (class "Default")
      (node (ref "JP6") (pin "1") (pinfunction "1_1") (pintype "passive"))
      (node (ref "R23") (pin "1") (pinfunction "1_1") (pintype "passive"))
    )
    (net (code "79") (name "Net-(JP6-Pad4)") (class "Default")
      (node (ref "JP6") (pin "4") (pinfunction "4_4") (pintype "passive"))
      (node (ref "R24") (pin "1") (pinfunction "1_1") (pintype "passive"))
    )
    (net (code "80") (name "Net-(JP6-Pad7)") (class "Default")
      (node (ref "JP6") (pin "7") (pinfunction "7_7") (pintype "passive"))
      (node (ref "R25") (pin "1") (pinfunction "1_1") (pintype "passive"))
    )
    (net (code "81") (name "Net-(JP6-Pad10)") (class "Default")
      (node (ref "JP6") (pin "10") (pinfunction "10_10") (pintype "passive"))
      (node (ref "R26") (pin "1") (pinfunction "1_1") (pintype "passive"))
    )
    (net (code "82") (name "Net-(LED1-PadC)") (class "Default")
      (node (ref "LED1") (pin "C") (pinfunction "C_C") (pintype "passive"))
      (node (ref "R10") (pin "1") (pinfunction "1_1") (pintype "passive"))
    )
    (net (code "83") (name "Net-(LED2-PadC)") (class "Default")
      (node (ref "LED2") (pin "C") (pinfunction "C_C") (pintype "passive"))
      (node (ref "R27") (pin "2") (pinfunction "2_2") (pintype "passive"))
    )
    (net (code "84") (name "Net-(Q1-D)") (class "Default")
      (node (ref "J1") (pin "1") (pinfunction "1_1") (pintype "passive"))
      (node (ref "Q1") (pin "3") (pinfunction "D_3") (pintype "passive"))
    )
    (net (code "85") (name "VCC") (class "Default")
      (node (ref "C1") (pin "1") (pinfunction "P$1_1") (pintype "passive"))
      (node (ref "JP3") (pin "2") (pinfunction "2_2") (pintype "passive"))
      (node (ref "JP4") (pin "2") (pinfunction "2_2") (pintype "passive"))
      (node (ref "LED1") (pin "A") (pinfunction "A_A") (pintype "passive"))
      (node (ref "R8") (pin "2") (pinfunction "2_2") (pintype "passive"))
      (node (ref "R9") (pin "2") (pinfunction "2_2") (pintype "passive"))
      (node (ref "SJ_A0") (pin "1") (pinfunction "1_1") (pintype "passive"))
      (node (ref "SJ_A1") (pin "1") (pinfunction "1_1") (pintype "passive"))
      (node (ref "SJ_A2") (pin "1") (pinfunction "1_1") (pintype "passive"))
      (node (ref "SJ_A3") (pin "1") (pinfunction "1_1") (pintype "passive"))
      (node (ref "SJ_A4") (pin "1") (pinfunction "1_1") (pintype "passive"))
      (node (ref "SJ_A5") (pin "1") (pinfunction "1_1") (pintype "passive"))
      (node (ref "U1") (pin "28") (pinfunction "VDD_28") (pintype "power_in"))
    )
    (net (code "86") (name "unconnected-(J2-Pad3)") (class "Default")
      (node (ref "J2") (pin "3") (pinfunction "3_3") (pintype "bidirectional"))
    )
    (net (code "87") (name "unconnected-(J2-Pad4)") (class "Default")
      (node (ref "J2") (pin "4") (pinfunction "4_4") (pintype "bidirectional"))
    )
    (net (code "88") (name "unconnected-(J2-Pad5)") (class "Default")
      (node (ref "J2") (pin "5") (pinfunction "5_5") (pintype "bidirectional"))
    )
    (net (code "89") (name "unconnected-(J2-Pad6)") (class "Default")
      (node (ref "J2") (pin "6") (pinfunction "6_6") (pintype "bidirectional"))
    )
    (net (code "90") (name "unconnected-(J2-Pad9)") (class "Default")
      (node (ref "J2") (pin "9") (pinfunction "9_9") (pintype "bidirectional"))
    )
    (net (code "91") (name "unconnected-(J2-Pad10)") (class "Default")
      (node (ref "J2") (pin "10") (pinfunction "10_10") (pintype "bidirectional"))
    )
    (net (code "92") (name "unconnected-(J2-Pad11)") (class "Default")
      (node (ref "J2") (pin "11") (pinfunction "11_11") (pintype "bidirectional"))
    )
    (net (code "93") (name "unconnected-(J2-Pad12)") (class "Default")
      (node (ref "J2") (pin "12") (pinfunction "12_12") (pintype "bidirectional"))
    )
    (net (code "94") (name "unconnected-(J2-Pad15)") (class "Default")
      (node (ref "J2") (pin "15") (pinfunction "15_15") (pintype "bidirectional"))
    )
    (net (code "95") (name "unconnected-(J2-Pad16)") (class "Default")
      (node (ref "J2") (pin "16") (pinfunction "16_16") (pintype "bidirectional"))
    )
    (net (code "96") (name "unconnected-(J2-Pad17)") (class "Default")
      (node (ref "J2") (pin "17") (pinfunction "17_17") (pintype "bidirectional"))
    )
    (net (code "97") (name "unconnected-(J2-Pad18)") (class "Default")
      (node (ref "J2") (pin "18") (pinfunction "18_18") (pintype "bidirectional"))
    )
    (net (code "98") (name "unconnected-(J2-Pad19)") (class "Default")
      (node (ref "J2") (pin "19") (pinfunction "19_19") (pintype "bidirectional"))
    )
    (net (code "99") (name "unconnected-(J2-Pad20)") (class "Default")
      (node (ref "J2") (pin "20") (pinfunction "20_20") (pintype "bidirectional"))
    )
    (net (code "100") (name "unconnected-(J2-Pad25)") (class "Default")
      (node (ref "J2") (pin "25") (pinfunction "25_25") (pintype "bidirectional"))
    )
    (net (code "101") (name "unconnected-(J2-Pad26)") (class "Default")
      (node (ref "J2") (pin "26") (pinfunction "26_26") (pintype "bidirectional"))
    )
    (net (code "102") (name "unconnected-(J2-Pad27)") (class "Default")
      (node (ref "J2") (pin "27") (pinfunction "27_27") (pintype "bidirectional"))
    )
    (net (code "103") (name "unconnected-(J2-Pad41)") (class "Default")
      (node (ref "J2") (pin "41") (pinfunction "41_41") (pintype "bidirectional"))
    )
    (net (code "104") (name "unconnected-(J2-Pad45)") (class "Default")
      (node (ref "J2") (pin "45") (pinfunction "45_45") (pintype "bidirectional"))
    )
    (net (code "105") (name "unconnected-(J2-Pad46)") (class "Default")
      (node (ref "J2") (pin "46") (pinfunction "46_46") (pintype "bidirectional"))
    )
    (net (code "106") (name "unconnected-(J2-Pad47)") (class "Default")
      (node (ref "J2") (pin "47") (pinfunction "47_47") (pintype "bidirectional"))
    )
    (net (code "107") (name "unconnected-(J2-Pad49)") (class "Default")
      (node (ref "J2") (pin "49") (pinfunction "49_49") (pintype "bidirectional"))
    )
    (net (code "108") (name "unconnected-(J2-Pad57)") (class "Default")
      (node (ref "J2") (pin "57") (pinfunction "57_57") (pintype "bidirectional"))
    )
    (net (code "109") (name "unconnected-(J2-Pad61)") (class "Default")
      (node (ref "J2") (pin "61") (pinfunction "61_61") (pintype "bidirectional"))
    )
    (net (code "110") (name "unconnected-(J2-Pad62)") (class "Default")
      (node (ref "J2") (pin "62") (pinfunction "62_62") (pintype "bidirectional"))
    )
    (net (code "111") (name "unconnected-(J2-Pad63)") (class "Default")
      (node (ref "J2") (pin "63") (pinfunction "63_63") (pintype "bidirectional"))
    )
    (net (code "112") (name "unconnected-(J2-Pad64)") (class "Default")
      (node (ref "J2") (pin "64") (pinfunction "64_64") (pintype "bidirectional"))
    )
    (net (code "113") (name "unconnected-(J2-Pad67)") (class "Default")
      (node (ref "J2") (pin "67") (pinfunction "67_67") (pintype "bidirectional"))
    )
    (net (code "114") (name "unconnected-(J2-Pad68)") (class "Default")
      (node (ref "J2") (pin "68") (pinfunction "68_68") (pintype "bidirectional"))
    )
    (net (code "115") (name "unconnected-(J2-Pad69)") (class "Default")
      (node (ref "J2") (pin "69") (pinfunction "69_69") (pintype "bidirectional"))
    )
    (net (code "116") (name "unconnected-(J2-Pad70)") (class "Default")
      (node (ref "J2") (pin "70") (pinfunction "70_70") (pintype "bidirectional"))
    )
    (net (code "117") (name "unconnected-(J2-Pad72)") (class "Default")
      (node (ref "J2") (pin "72") (pinfunction "72_72") (pintype "bidirectional"))
    )
    (net (code "118") (name "unconnected-(J2-Pad73)") (class "Default")
      (node (ref "J2") (pin "73") (pinfunction "73_73") (pintype "bidirectional"))
    )
    (net (code "119") (name "unconnected-(J2-Pad75)") (class "Default")
      (node (ref "J2") (pin "75") (pinfunction "75_75") (pintype "bidirectional"))
    )
    (net (code "120") (name "unconnected-(J2-Pad76)") (class "Default")
      (node (ref "J2") (pin "76") (pinfunction "76_76") (pintype "bidirectional"))
    )
    (net (code "121") (name "unconnected-(J2-Pad89)") (class "Default")
      (node (ref "J2") (pin "89") (pinfunction "89_89") (pintype "bidirectional"))
    )
    (net (code "122") (name "unconnected-(J2-Pad91)") (class "Default")
      (node (ref "J2") (pin "91") (pinfunction "91_91") (pintype "bidirectional"))
    )
    (net (code "123") (name "unconnected-(J2-Pad92)") (class "Default")
      (node (ref "J2") (pin "92") (pinfunction "92_92") (pintype "bidirectional"))
    )
    (net (code "124") (name "unconnected-(J2-Pad93)") (class "Default")
      (node (ref "J2") (pin "93") (pinfunction "93_93") (pintype "bidirectional"))
    )
    (net (code "125") (name "unconnected-(J2-Pad94)") (class "Default")
      (node (ref "J2") (pin "94") (pinfunction "94_94") (pintype "bidirectional"))
    )
    (net (code "126") (name "unconnected-(J2-Pad95)") (class "Default")
      (node (ref "J2") (pin "95") (pinfunction "95_95") (pintype "bidirectional"))
    )
    (net (code "127") (name "unconnected-(J2-Pad96)") (class "Default")
      (node (ref "J2") (pin "96") (pinfunction "96_96") (pintype "bidirectional"))
    )
    (net (code "128") (name "unconnected-(J2-Pad97)") (class "Default")
      (node (ref "J2") (pin "97") (pinfunction "97_97") (pintype "bidirectional"))
    )
    (net (code "129") (name "unconnected-(J2-Pad100)") (class "Default")
      (node (ref "J2") (pin "100") (pinfunction "100_100") (pintype "bidirectional"))
    )
    (net (code "130") (name "unconnected-(J3-Pad1)") (class "Default")
      (node (ref "J3") (pin "1") (pinfunction "1_1") (pintype "bidirectional"))
    )
    (net (code "131") (name "unconnected-(J3-Pad2)") (class "Default")
      (node (ref "J3") (pin "2") (pinfunction "2_2") (pintype "bidirectional"))
    )
    (net (code "132") (name "unconnected-(J3-Pad3)") (class "Default")
      (node (ref "J3") (pin "3") (pinfunction "3_3") (pintype "bidirectional"))
    )
    (net (code "133") (name "unconnected-(J3-Pad4)") (class "Default")
      (node (ref "J3") (pin "4") (pinfunction "4_4") (pintype "bidirectional"))
    )
    (net (code "134") (name "unconnected-(J3-Pad5)") (class "Default")
      (node (ref "J3") (pin "5") (pinfunction "5_5") (pintype "bidirectional"))
    )
    (net (code "135") (name "unconnected-(J3-Pad6)") (class "Default")
      (node (ref "J3") (pin "6") (pinfunction "6_6") (pintype "bidirectional"))
    )
    (net (code "136") (name "unconnected-(J3-Pad9)") (class "Default")
      (node (ref "J3") (pin "9") (pinfunction "9_9") (pintype "bidirectional"))
    )
    (net (code "137") (name "unconnected-(J3-Pad10)") (class "Default")
      (node (ref "J3") (pin "10") (pinfunction "10_10") (pintype "bidirectional"))
    )
    (net (code "138") (name "unconnected-(J3-Pad11)") (class "Default")
      (node (ref "J3") (pin "11") (pinfunction "11_11") (pintype "bidirectional"))
    )
    (net (code "139") (name "unconnected-(J3-Pad12)") (class "Default")
      (node (ref "J3") (pin "12") (pinfunction "12_12") (pintype "bidirectional"))
    )
    (net (code "140") (name "unconnected-(J3-Pad15)") (class "Default")
      (node (ref "J3") (pin "15") (pinfunction "15_15") (pintype "bidirectional"))
    )
    (net (code "141") (name "unconnected-(J3-Pad16)") (class "Default")
      (node (ref "J3") (pin "16") (pinfunction "16_16") (pintype "bidirectional"))
    )
    (net (code "142") (name "unconnected-(J3-Pad17)") (class "Default")
      (node (ref "J3") (pin "17") (pinfunction "17_17") (pintype "bidirectional"))
    )
    (net (code "143") (name "unconnected-(J3-Pad18)") (class "Default")
      (node (ref "J3") (pin "18") (pinfunction "18_18") (pintype "bidirectional"))
    )
    (net (code "144") (name "unconnected-(J3-Pad21)") (class "Default")
      (node (ref "J3") (pin "21") (pinfunction "21_21") (pintype "bidirectional"))
    )
    (net (code "145") (name "unconnected-(J3-Pad22)") (class "Default")
      (node (ref "J3") (pin "22") (pinfunction "22_22") (pintype "bidirectional"))
    )
    (net (code "146") (name "unconnected-(J3-Pad23)") (class "Default")
      (node (ref "J3") (pin "23") (pinfunction "23_23") (pintype "bidirectional"))
    )
    (net (code "147") (name "unconnected-(J3-Pad24)") (class "Default")
      (node (ref "J3") (pin "24") (pinfunction "24_24") (pintype "bidirectional"))
    )
    (net (code "148") (name "unconnected-(J3-Pad43)") (class "Default")
      (node (ref "J3") (pin "43") (pinfunction "43_43") (pintype "bidirectional"))
    )
    (net (code "149") (name "unconnected-(J3-Pad45)") (class "Default")
      (node (ref "J3") (pin "45") (pinfunction "45_45") (pintype "bidirectional"))
    )
    (net (code "150") (name "unconnected-(J3-Pad46)") (class "Default")
      (node (ref "J3") (pin "46") (pinfunction "46_46") (pintype "bidirectional"))
    )
    (net (code "151") (name "unconnected-(J3-Pad47)") (class "Default")
      (node (ref "J3") (pin "47") (pinfunction "47_47") (pintype "bidirectional"))
    )
    (net (code "152") (name "unconnected-(J3-Pad48)") (class "Default")
      (node (ref "J3") (pin "48") (pinfunction "48_48") (pintype "bidirectional"))
    )
    (net (code "153") (name "unconnected-(J3-Pad49)") (class "Default")
      (node (ref "J3") (pin "49") (pinfunction "49_49") (pintype "bidirectional"))
    )
    (net (code "154") (name "unconnected-(J3-Pad51)") (class "Default")
      (node (ref "J3") (pin "51") (pinfunction "51_51") (pintype "bidirectional"))
    )
    (net (code "155") (name "unconnected-(J3-Pad52)") (class "Default")
      (node (ref "J3") (pin "52") (pinfunction "52_52") (pintype "bidirectional"))
    )
    (net (code "156") (name "unconnected-(J3-Pad53)") (class "Default")
      (node (ref "J3") (pin "53") (pinfunction "53_53") (pintype "bidirectional"))
    )
    (net (code "157") (name "unconnected-(J3-Pad54)") (class "Default")
      (node (ref "J3") (pin "54") (pinfunction "54_54") (pintype "bidirectional"))
    )
    (net (code "158") (name "unconnected-(J3-Pad57)") (class "Default")
      (node (ref "J3") (pin "57") (pinfunction "57_57") (pintype "bidirectional"))
    )
    (net (code "159") (name "unconnected-(J3-Pad58)") (class "Default")
      (node (ref "J3") (pin "58") (pinfunction "58_58") (pintype "bidirectional"))
    )
    (net (code "160") (name "unconnected-(J3-Pad59)") (class "Default")
      (node (ref "J3") (pin "59") (pinfunction "59_59") (pintype "bidirectional"))
    )
    (net (code "161") (name "unconnected-(J3-Pad60)") (class "Default")
      (node (ref "J3") (pin "60") (pinfunction "60_60") (pintype "bidirectional"))
    )
    (net (code "162") (name "unconnected-(J3-Pad63)") (class "Default")
      (node (ref "J3") (pin "63") (pinfunction "63_63") (pintype "bidirectional"))
    )
    (net (code "163") (name "unconnected-(J3-Pad64)") (class "Default")
      (node (ref "J3") (pin "64") (pinfunction "64_64") (pintype "bidirectional"))
    )
    (net (code "164") (name "unconnected-(J3-Pad65)") (class "Default")
      (node (ref "J3") (pin "65") (pinfunction "65_65") (pintype "bidirectional"))
    )
    (net (code "165") (name "unconnected-(J3-Pad66)") (class "Default")
      (node (ref "J3") (pin "66") (pinfunction "66_66") (pintype "bidirectional"))
    )
    (net (code "166") (name "unconnected-(J3-Pad69)") (class "Default")
      (node (ref "J3") (pin "69") (pinfunction "69_69") (pintype "bidirectional"))
    )
    (net (code "167") (name "unconnected-(J3-Pad70)") (class "Default")
      (node (ref "J3") (pin "70") (pinfunction "70_70") (pintype "bidirectional"))
    )
    (net (code "168") (name "unconnected-(J3-Pad71)") (class "Default")
      (node (ref "J3") (pin "71") (pinfunction "71_71") (pintype "bidirectional"))
    )
    (net (code "169") (name "unconnected-(J3-Pad72)") (class "Default")
      (node (ref "J3") (pin "72") (pinfunction "72_72") (pintype "bidirectional"))
    )
    (net (code "170") (name "unconnected-(J3-Pad75)") (class "Default")
      (node (ref "J3") (pin "75") (pinfunction "75_75") (pintype "bidirectional"))
    )
    (net (code "171") (name "unconnected-(J3-Pad76)") (class "Default")
      (node (ref "J3") (pin "76") (pinfunction "76_76") (pintype "bidirectional"))
    )
    (net (code "172") (name "unconnected-(J3-Pad77)") (class "Default")
      (node (ref "J3") (pin "77") (pinfunction "77_77") (pintype "bidirectional"))
    )
    (net (code "173") (name "unconnected-(J3-Pad78)") (class "Default")
      (node (ref "J3") (pin "78") (pinfunction "78_78") (pintype "bidirectional"))
    )
    (net (code "174") (name "unconnected-(J3-Pad81)") (class "Default")
      (node (ref "J3") (pin "81") (pinfunction "81_81") (pintype "bidirectional"))
    )
    (net (code "175") (name "unconnected-(J3-Pad82)") (class "Default")
      (node (ref "J3") (pin "82") (pinfunction "82_82") (pintype "bidirectional"))
    )
    (net (code "176") (name "unconnected-(J3-Pad83)") (class "Default")
      (node (ref "J3") (pin "83") (pinfunction "83_83") (pintype "bidirectional"))
    )
    (net (code "177") (name "unconnected-(J3-Pad84)") (class "Default")
      (node (ref "J3") (pin "84") (pinfunction "84_84") (pintype "bidirectional"))
    )
    (net (code "178") (name "unconnected-(J3-Pad87)") (class "Default")
      (node (ref "J3") (pin "87") (pinfunction "87_87") (pintype "bidirectional"))
    )
    (net (code "179") (name "unconnected-(J3-Pad88)") (class "Default")
      (node (ref "J3") (pin "88") (pinfunction "88_88") (pintype "bidirectional"))
    )
    (net (code "180") (name "unconnected-(J3-Pad89)") (class "Default")
      (node (ref "J3") (pin "89") (pinfunction "89_89") (pintype "bidirectional"))
    )
    (net (code "181") (name "unconnected-(J3-Pad90)") (class "Default")
      (node (ref "J3") (pin "90") (pinfunction "90_90") (pintype "bidirectional"))
    )
    (net (code "182") (name "unconnected-(J3-Pad93)") (class "Default")
      (node (ref "J3") (pin "93") (pinfunction "93_93") (pintype "bidirectional"))
    )
    (net (code "183") (name "unconnected-(J3-Pad94)") (class "Default")
      (node (ref "J3") (pin "94") (pinfunction "94_94") (pintype "bidirectional"))
    )
    (net (code "184") (name "unconnected-(J3-Pad95)") (class "Default")
      (node (ref "J3") (pin "95") (pinfunction "95_95") (pintype "bidirectional"))
    )
    (net (code "185") (name "unconnected-(J3-Pad96)") (class "Default")
      (node (ref "J3") (pin "96") (pinfunction "96_96") (pintype "bidirectional"))
    )
    (net (code "186") (name "unconnected-(J3-Pad99)") (class "Default")
      (node (ref "J3") (pin "99") (pinfunction "99_99") (pintype "bidirectional"))
    )
    (net (code "187") (name "unconnected-(J3-Pad100)") (class "Default")
      (node (ref "J3") (pin "100") (pinfunction "100_100") (pintype "bidirectional"))
    )
    (net (code "188") (name "unconnected-(X1AH-KL-Pad4)") (class "Default")
      (node (ref "X1") (pin "4") (pinfunction "KL_4") (pintype "passive"))
    )
    (net (code "189") (name "unconnected-(X1AJ-KL-Pad5)") (class "Default")
      (node (ref "X1") (pin "5") (pinfunction "KL_5") (pintype "passive"))
    )
    (net (code "190") (name "unconnected-(X1AK-KL-Pad6)") (class "Default")
      (node (ref "X1") (pin "6") (pinfunction "KL_6") (pintype "passive"))
    )
    (net (code "191") (name "unconnected-(X1F-KL-Pad14)") (class "Default")
      (node (ref "X1") (pin "14") (pinfunction "KL_14") (pintype "passive"))
    )
    (net (code "192") (name "unconnected-(X1I-KL-Pad17)") (class "Default")
      (node (ref "X1") (pin "17") (pinfunction "KL_17") (pintype "passive"))
    )
    (net (code "193") (name "unconnected-(X1K-KL-Pad19)") (class "Default")
      (node (ref "X1") (pin "19") (pinfunction "KL_19") (pintype "passive"))
    )
    (net (code "194") (name "unconnected-(X1M-KL-Pad20)") (class "Default")
      (node (ref "X1") (pin "20") (pinfunction "KL_20") (pintype "passive"))
    )
    (net (code "195") (name "unconnected-(X1N-KL-Pad21)") (class "Default")
      (node (ref "X1") (pin "21") (pinfunction "KL_21") (pintype "passive"))
    )
    (net (code "196") (name "unconnected-(X1O-KL-Pad22)") (class "Default")
      (node (ref "X1") (pin "22") (pinfunction "KL_22") (pintype "passive"))
    )
    (net (code "197") (name "unconnected-(X1P-KL-Pad23)") (class "Default")
      (node (ref "X1") (pin "23") (pinfunction "KL_23") (pintype "passive"))
    )
    (net (code "198") (name "unconnected-(X1Q-KL-Pad24)") (class "Default")
      (node (ref "X1") (pin "24") (pinfunction "KL_24") (pintype "passive"))
    )
    (net (code "199") (name "unconnected-(X1R-KL-Pad25)") (class "Default")
      (node (ref "X1") (pin "25") (pinfunction "KL_25") (pintype "passive"))
    )
    (net (code "200") (name "unconnected-(X1S-KL-Pad26)") (class "Default")
      (node (ref "X1") (pin "26") (pinfunction "KL_26") (pintype "passive"))
    )
    (net (code "201") (name "unconnected-(X1T-KL-Pad27)") (class "Default")
      (node (ref "X1") (pin "27") (pinfunction "KL_27") (pintype "passive"))
    )
    (net (code "202") (name "unconnected-(X1U-KL-Pad28)") (class "Default")
      (node (ref "X1") (pin "28") (pinfunction "KL_28") (pintype "passive"))
    )
    (net (code "203") (name "unconnected-(X1V-KL-Pad29)") (class "Default")
      (node (ref "X1") (pin "29") (pinfunction "KL_29") (pintype "passive"))
    )
    (net (code "204") (name "unconnected-(X1X-KL-Pad30)") (class "Default")
      (node (ref "X1") (pin "30") (pinfunction "KL_30") (pintype "passive"))
    )
    (net (code "205") (name "unconnected-(X1Y-KL-Pad31)") (class "Default")
      (node (ref "X1") (pin "31") (pinfunction "KL_31") (pintype "passive"))
    )
  )
)
